# M705.net
KiCad netlist of a schematic drawn in EAGLE
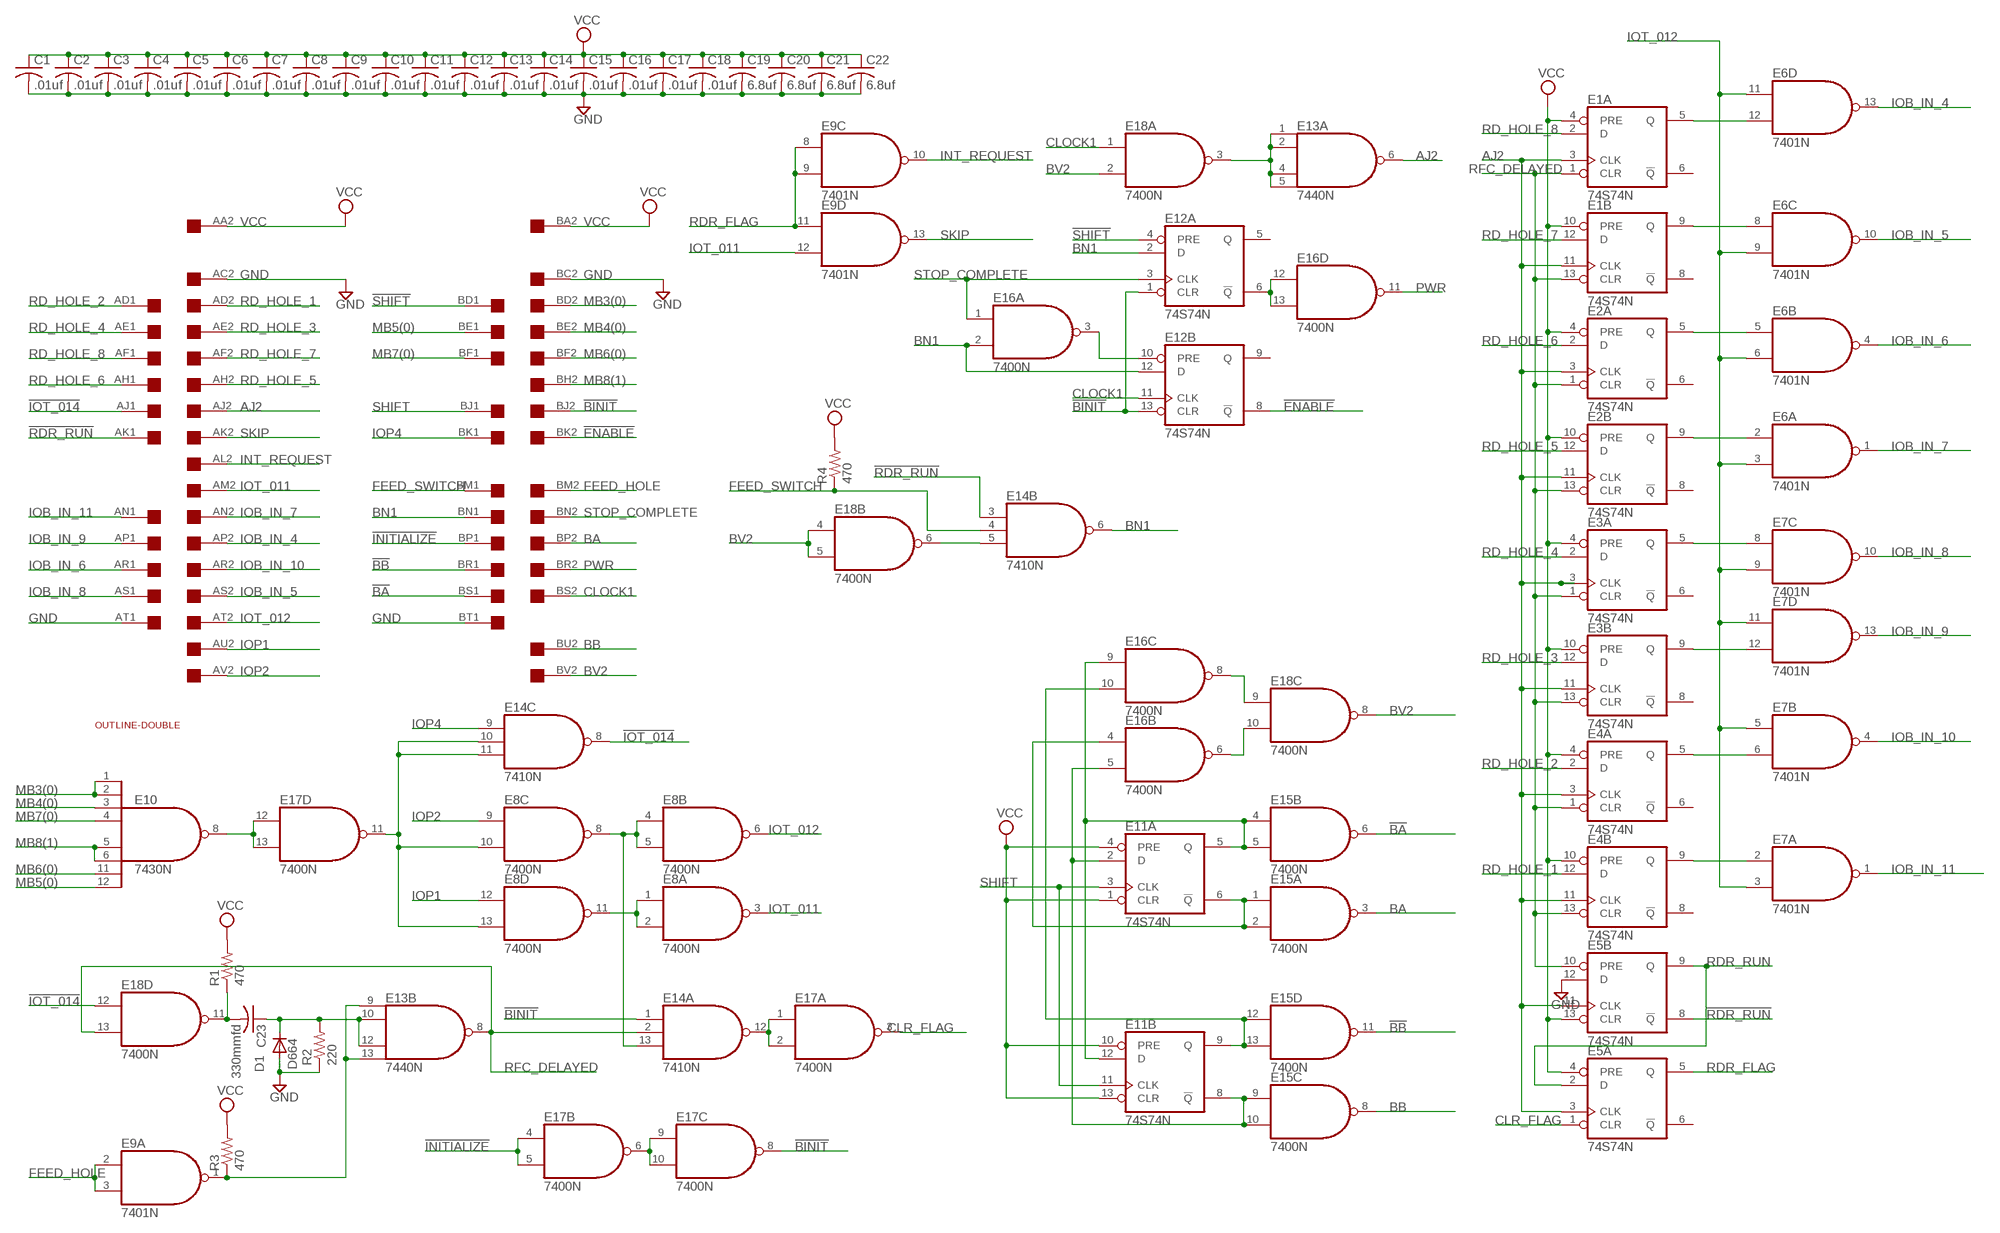
[diagram p0: schematic, sheet 1]

(export (version "E")
  (design (tool "Eeschema 10.0.6"))
  (components
    (comp (ref "C1")
      (value ".01uf")
      (footprint "eagle-import:C050-025X075")
      (libsource (lib "eagle-import") (part "C-US050-025X075"))
    )
    (comp (ref "C2")
      (value ".01uf")
      (footprint "eagle-import:C050-025X075")
      (libsource (lib "eagle-import") (part "C-US050-025X075"))
    )
    (comp (ref "C3")
      (value ".01uf")
      (footprint "eagle-import:C050-025X075")
      (libsource (lib "eagle-import") (part "C-US050-025X075"))
    )
    (comp (ref "C4")
      (value ".01uf")
      (footprint "eagle-import:C050-025X075")
      (libsource (lib "eagle-import") (part "C-US050-025X075"))
    )
    (comp (ref "C5")
      (value ".01uf")
      (footprint "eagle-import:C050-025X075")
      (libsource (lib "eagle-import") (part "C-US050-025X075"))
    )
    (comp (ref "C6")
      (value ".01uf")
      (footprint "eagle-import:C050-025X075")
      (libsource (lib "eagle-import") (part "C-US050-025X075"))
    )
    (comp (ref "C7")
      (value ".01uf")
      (footprint "eagle-import:C050-025X075")
      (libsource (lib "eagle-import") (part "C-US050-025X075"))
    )
    (comp (ref "C8")
      (value ".01uf")
      (footprint "eagle-import:C050-025X075")
      (libsource (lib "eagle-import") (part "C-US050-025X075"))
    )
    (comp (ref "C9")
      (value ".01uf")
      (footprint "eagle-import:C050-025X075")
      (libsource (lib "eagle-import") (part "C-US050-025X075"))
    )
    (comp (ref "C10")
      (value ".01uf")
      (footprint "eagle-import:C050-025X075")
      (libsource (lib "eagle-import") (part "C-US050-025X075"))
    )
    (comp (ref "C11")
      (value ".01uf")
      (footprint "eagle-import:C050-025X075")
      (libsource (lib "eagle-import") (part "C-US050-025X075"))
    )
    (comp (ref "C12")
      (value ".01uf")
      (footprint "eagle-import:C050-025X075")
      (libsource (lib "eagle-import") (part "C-US050-025X075"))
    )
    (comp (ref "C13")
      (value ".01uf")
      (footprint "eagle-import:C050-025X075")
      (libsource (lib "eagle-import") (part "C-US050-025X075"))
    )
    (comp (ref "C14")
      (value ".01uf")
      (footprint "eagle-import:C050-025X075")
      (libsource (lib "eagle-import") (part "C-US050-025X075"))
    )
    (comp (ref "C15")
      (value ".01uf")
      (footprint "eagle-import:C050-025X075")
      (libsource (lib "eagle-import") (part "C-US050-025X075"))
    )
    (comp (ref "C16")
      (value ".01uf")
      (footprint "eagle-import:C050-025X075")
      (libsource (lib "eagle-import") (part "C-US050-025X075"))
    )
    (comp (ref "C17")
      (value ".01uf")
      (footprint "eagle-import:C050-025X075")
      (libsource (lib "eagle-import") (part "C-US050-025X075"))
    )
    (comp (ref "C18")
      (value ".01uf")
      (footprint "eagle-import:C050-025X075")
      (libsource (lib "eagle-import") (part "C-US050-025X075"))
    )
    (comp (ref "C19")
      (value "6.8uf")
      (footprint "eagle-import:C150-054X183")
      (libsource (lib "eagle-import") (part "C-US150-054X183"))
    )
    (comp (ref "C20")
      (value "6.8uf")
      (footprint "eagle-import:C150-054X183")
      (libsource (lib "eagle-import") (part "C-US150-054X183"))
    )
    (comp (ref "C21")
      (value "6.8uf")
      (footprint "eagle-import:C150-054X183")
      (libsource (lib "eagle-import") (part "C-US150-054X183"))
    )
    (comp (ref "C22")
      (value "6.8uf")
      (footprint "eagle-import:C150-054X183")
      (libsource (lib "eagle-import") (part "C-US150-054X183"))
    )
    (comp (ref "C23")
      (value "330mmfd")
      (footprint "eagle-import:C050-025X075")
      (libsource (lib "eagle-import") (part "C-US050-025X075"))
    )
    (comp (ref "D1")
      (value "D664")
      (footprint "eagle-import:DO35-10")
      (libsource (lib "eagle-import") (part "1N4148DO35-10"))
    )
    (comp (ref "E1")
      (value "74S74N")
      (footprint "eagle-import:DIL14")
      (libsource (lib "eagle-import") (part "7474NS"))
    )
    (comp (ref "E2")
      (value "74S74N")
      (footprint "eagle-import:DIL14")
      (libsource (lib "eagle-import") (part "7474NS"))
    )
    (comp (ref "E3")
      (value "74S74N")
      (footprint "eagle-import:DIL14")
      (libsource (lib "eagle-import") (part "7474NS"))
    )
    (comp (ref "E4")
      (value "74S74N")
      (footprint "eagle-import:DIL14")
      (libsource (lib "eagle-import") (part "7474NS"))
    )
    (comp (ref "E5")
      (value "74S74N")
      (footprint "eagle-import:DIL14")
      (libsource (lib "eagle-import") (part "7474NS"))
    )
    (comp (ref "E6")
      (value "7401N")
      (footprint "eagle-import:DIL14")
      (libsource (lib "eagle-import") (part "7401NLS"))
    )
    (comp (ref "E7")
      (value "7401N")
      (footprint "eagle-import:DIL14")
      (libsource (lib "eagle-import") (part "7401NLS"))
    )
    (comp (ref "E8")
      (value "7400N")
      (footprint "eagle-import:DIL14")
      (libsource (lib "eagle-import") (part "7400N"))
    )
    (comp (ref "E9")
      (value "7401N")
      (footprint "eagle-import:DIL14")
      (libsource (lib "eagle-import") (part "7401NLS"))
    )
    (comp (ref "E10")
      (value "7430N")
      (footprint "eagle-import:DIL14")
      (libsource (lib "eagle-import") (part "7430N"))
    )
    (comp (ref "E11")
      (value "74S74N")
      (footprint "eagle-import:DIL14")
      (libsource (lib "eagle-import") (part "7474NS"))
    )
    (comp (ref "E12")
      (value "74S74N")
      (footprint "eagle-import:DIL14")
      (libsource (lib "eagle-import") (part "7474NS"))
    )
    (comp (ref "E13")
      (value "7440N")
      (footprint "eagle-import:DIL14")
      (libsource (lib "eagle-import") (part "7420NS"))
    )
    (comp (ref "E14")
      (value "7410N")
      (footprint "eagle-import:DIL14")
      (libsource (lib "eagle-import") (part "7410N"))
    )
    (comp (ref "E15")
      (value "7400N")
      (footprint "eagle-import:DIL14")
      (libsource (lib "eagle-import") (part "7400N"))
    )
    (comp (ref "E16")
      (value "7400N")
      (footprint "eagle-import:DIL14")
      (libsource (lib "eagle-import") (part "7400N"))
    )
    (comp (ref "E17")
      (value "7400N")
      (footprint "eagle-import:DIL14")
      (libsource (lib "eagle-import") (part "7400N"))
    )
    (comp (ref "E18")
      (value "7400N")
      (footprint "eagle-import:DIL14")
      (libsource (lib "eagle-import") (part "7400N"))
    )
    (comp (ref "R1")
      (value "470")
      (footprint "eagle-import:0207_10")
      (libsource (lib "eagle-import") (part "R-US_0207/10"))
    )
    (comp (ref "R2")
      (value "220")
      (footprint "eagle-import:0207_10")
      (libsource (lib "eagle-import") (part "R-US_0207/10"))
    )
    (comp (ref "R3")
      (value "470")
      (footprint "eagle-import:0207_10")
      (libsource (lib "eagle-import") (part "R-US_0207/10"))
    )
    (comp (ref "R4")
      (value "470")
      (footprint "eagle-import:0207_10")
      (libsource (lib "eagle-import") (part "R-US_0207/10"))
    )
    (comp (ref "U$5")
      (value "DOUBLE")
      (footprint "eagle-import:EDGE-CON4")
      (libsource (lib "eagle-import") (part "DOUBLE"))
    )
    (comp (ref "U$6")
      (value "OUTLINE-DOUBLE")
      (footprint "eagle-import:DOUBLE")
      (libsource (lib "eagle-import") (part "OUTLINE-DOUBLE"))
    )
  )
  (nets
    (net (code "1") (name "/AJ2") (class "Default")
      (node (ref "E1") (pin "11") (pinfunction "CLK_11") (pintype "input"))
      (node (ref "E1") (pin "3") (pinfunction "CLK_3") (pintype "input"))
      (node (ref "E13") (pin "6") (pinfunction "O_6") (pintype "output"))
      (node (ref "E2") (pin "11") (pinfunction "CLK_11") (pintype "input"))
      (node (ref "E2") (pin "3") (pinfunction "CLK_3") (pintype "input"))
      (node (ref "E3") (pin "11") (pinfunction "CLK_11") (pintype "input"))
      (node (ref "E3") (pin "3") (pinfunction "CLK_3") (pintype "input"))
      (node (ref "E4") (pin "11") (pinfunction "CLK_11") (pintype "input"))
      (node (ref "E4") (pin "3") (pinfunction "CLK_3") (pintype "input"))
      (node (ref "E5") (pin "11") (pinfunction "CLK_11") (pintype "input"))
      (node (ref "E5") (pin "3") (pinfunction "CLK_3") (pintype "input"))
      (node (ref "U$5") (pin "AJ2") (pinfunction "1_AJ2") (pintype "bidirectional"))
    )
    (net (code "2") (name "/BA") (class "Default")
      (node (ref "E15") (pin "3") (pinfunction "O_3") (pintype "output"))
      (node (ref "U$5") (pin "BP2") (pinfunction "1_BP2") (pintype "bidirectional"))
    )
    (net (code "3") (name "/BB") (class "Default")
      (node (ref "E15") (pin "8") (pinfunction "O_8") (pintype "output"))
      (node (ref "U$5") (pin "BU2") (pinfunction "1_BU2") (pintype "bidirectional"))
    )
    (net (code "4") (name "/BN1") (class "Default")
      (node (ref "E12") (pin "12") (pinfunction "D_12") (pintype "input"))
      (node (ref "E12") (pin "2") (pinfunction "D_2") (pintype "input"))
      (node (ref "E14") (pin "6") (pinfunction "O_6") (pintype "output"))
      (node (ref "E16") (pin "2") (pinfunction "I1_2") (pintype "input"))
      (node (ref "U$5") (pin "BN1") (pinfunction "1_BN1") (pintype "bidirectional"))
    )
    (net (code "5") (name "/BV2") (class "Default")
      (node (ref "E18") (pin "2") (pinfunction "I1_2") (pintype "input"))
      (node (ref "E18") (pin "4") (pinfunction "I0_4") (pintype "input"))
      (node (ref "E18") (pin "5") (pinfunction "I1_5") (pintype "input"))
      (node (ref "E18") (pin "8") (pinfunction "O_8") (pintype "output"))
      (node (ref "U$5") (pin "BV2") (pinfunction "1_BV2") (pintype "bidirectional"))
    )
    (net (code "6") (name "/CLOCK1") (class "Default")
      (node (ref "E12") (pin "11") (pinfunction "CLK_11") (pintype "input"))
      (node (ref "E18") (pin "1") (pinfunction "I0_1") (pintype "input"))
      (node (ref "U$5") (pin "BS2") (pinfunction "1_BS2") (pintype "bidirectional"))
    )
    (net (code "7") (name "/CLR_FLAG") (class "Default")
      (node (ref "E17") (pin "3") (pinfunction "O_3") (pintype "output"))
      (node (ref "E5") (pin "1") (pinfunction "CLR_1") (pintype "input"))
    )
    (net (code "8") (name "/FEED_HOLE") (class "Default")
      (node (ref "E9") (pin "2") (pinfunction "I0_2") (pintype "input"))
      (node (ref "E9") (pin "3") (pinfunction "I1_3") (pintype "input"))
      (node (ref "U$5") (pin "BM2") (pinfunction "1_BM2") (pintype "bidirectional"))
    )
    (net (code "9") (name "/FEED_SWITCH") (class "Default")
      (node (ref "E14") (pin "4") (pinfunction "I1_4") (pintype "input"))
      (node (ref "R4") (pin "1") (pinfunction "1_1") (pintype "passive"))
      (node (ref "U$5") (pin "BM1") (pinfunction "1_BM1") (pintype "bidirectional"))
    )
    (net (code "10") (name "/INT_REQUEST") (class "Default")
      (node (ref "E9") (pin "10") (pinfunction "O_10") (pintype "open_collector"))
      (node (ref "U$5") (pin "AL2") (pinfunction "1_AL2") (pintype "bidirectional"))
    )
    (net (code "11") (name "/IOB_IN_4") (class "Default")
      (node (ref "E6") (pin "13") (pinfunction "O_13") (pintype "open_collector"))
      (node (ref "U$5") (pin "AP2") (pinfunction "1_AP2") (pintype "bidirectional"))
    )
    (net (code "12") (name "/IOB_IN_5") (class "Default")
      (node (ref "E6") (pin "10") (pinfunction "O_10") (pintype "open_collector"))
      (node (ref "U$5") (pin "AS2") (pinfunction "1_AS2") (pintype "bidirectional"))
    )
    (net (code "13") (name "/IOB_IN_6") (class "Default")
      (node (ref "E6") (pin "4") (pinfunction "O_4") (pintype "open_collector"))
      (node (ref "U$5") (pin "AR1") (pinfunction "1_AR1") (pintype "bidirectional"))
    )
    (net (code "14") (name "/IOB_IN_7") (class "Default")
      (node (ref "E6") (pin "1") (pinfunction "O_1") (pintype "open_collector"))
      (node (ref "U$5") (pin "AN2") (pinfunction "1_AN2") (pintype "bidirectional"))
    )
    (net (code "15") (name "/IOB_IN_8") (class "Default")
      (node (ref "E7") (pin "10") (pinfunction "O_10") (pintype "open_collector"))
      (node (ref "U$5") (pin "AS1") (pinfunction "1_AS1") (pintype "bidirectional"))
    )
    (net (code "16") (name "/IOB_IN_9") (class "Default")
      (node (ref "E7") (pin "13") (pinfunction "O_13") (pintype "open_collector"))
      (node (ref "U$5") (pin "AP1") (pinfunction "1_AP1") (pintype "bidirectional"))
    )
    (net (code "17") (name "/IOB_IN_10") (class "Default")
      (node (ref "E7") (pin "4") (pinfunction "O_4") (pintype "open_collector"))
      (node (ref "U$5") (pin "AR2") (pinfunction "1_AR2") (pintype "bidirectional"))
    )
    (net (code "18") (name "/IOB_IN_11") (class "Default")
      (node (ref "E7") (pin "1") (pinfunction "O_1") (pintype "open_collector"))
      (node (ref "U$5") (pin "AN1") (pinfunction "1_AN1") (pintype "bidirectional"))
    )
    (net (code "19") (name "/IOP1") (class "Default")
      (node (ref "E8") (pin "12") (pinfunction "I0_12") (pintype "input"))
      (node (ref "U$5") (pin "AU2") (pinfunction "1_AU2") (pintype "bidirectional"))
    )
    (net (code "20") (name "/IOP2") (class "Default")
      (node (ref "E8") (pin "9") (pinfunction "I0_9") (pintype "input"))
      (node (ref "U$5") (pin "AV2") (pinfunction "1_AV2") (pintype "bidirectional"))
    )
    (net (code "21") (name "/IOP4") (class "Default")
      (node (ref "E14") (pin "9") (pinfunction "I0_9") (pintype "input"))
      (node (ref "U$5") (pin "BK1") (pinfunction "1_BK1") (pintype "bidirectional"))
    )
    (net (code "22") (name "/IOT_011") (class "Default")
      (node (ref "E8") (pin "3") (pinfunction "O_3") (pintype "output"))
      (node (ref "E9") (pin "12") (pinfunction "I1_12") (pintype "input"))
      (node (ref "U$5") (pin "AM2") (pinfunction "1_AM2") (pintype "bidirectional"))
    )
    (net (code "23") (name "/IOT_012") (class "Default")
      (node (ref "E6") (pin "11") (pinfunction "I0_11") (pintype "input"))
      (node (ref "E6") (pin "3") (pinfunction "I1_3") (pintype "input"))
      (node (ref "E6") (pin "6") (pinfunction "I1_6") (pintype "input"))
      (node (ref "E6") (pin "9") (pinfunction "I1_9") (pintype "input"))
      (node (ref "E7") (pin "11") (pinfunction "I0_11") (pintype "input"))
      (node (ref "E7") (pin "3") (pinfunction "I1_3") (pintype "input"))
      (node (ref "E7") (pin "5") (pinfunction "I0_5") (pintype "input"))
      (node (ref "E7") (pin "9") (pinfunction "I1_9") (pintype "input"))
      (node (ref "E8") (pin "6") (pinfunction "O_6") (pintype "output"))
      (node (ref "U$5") (pin "AT2") (pinfunction "1_AT2") (pintype "bidirectional"))
    )
    (net (code "24") (name "/MB3(0)") (class "Default")
      (node (ref "E10") (pin "1") (pinfunction "I0_1") (pintype "input"))
      (node (ref "E10") (pin "2") (pinfunction "I1_2") (pintype "input"))
      (node (ref "U$5") (pin "BD2") (pinfunction "1_BD2") (pintype "bidirectional"))
    )
    (net (code "25") (name "/MB4(0)") (class "Default")
      (node (ref "E10") (pin "3") (pinfunction "I2_3") (pintype "input"))
      (node (ref "U$5") (pin "BE2") (pinfunction "1_BE2") (pintype "bidirectional"))
    )
    (net (code "26") (name "/MB5(0)") (class "Default")
      (node (ref "E10") (pin "12") (pinfunction "I7_12") (pintype "input"))
      (node (ref "U$5") (pin "BE1") (pinfunction "1_BE1") (pintype "bidirectional"))
    )
    (net (code "27") (name "/MB6(0)") (class "Default")
      (node (ref "E10") (pin "11") (pinfunction "I6_11") (pintype "input"))
      (node (ref "U$5") (pin "BF2") (pinfunction "1_BF2") (pintype "bidirectional"))
    )
    (net (code "28") (name "/MB7(0)") (class "Default")
      (node (ref "E10") (pin "4") (pinfunction "I3_4") (pintype "input"))
      (node (ref "U$5") (pin "BF1") (pinfunction "1_BF1") (pintype "bidirectional"))
    )
    (net (code "29") (name "/MB8(1)") (class "Default")
      (node (ref "E10") (pin "5") (pinfunction "I4_5") (pintype "input"))
      (node (ref "E10") (pin "6") (pinfunction "I5_6") (pintype "input"))
      (node (ref "U$5") (pin "BH2") (pinfunction "1_BH2") (pintype "bidirectional"))
    )
    (net (code "30") (name "/PWR") (class "Default")
      (node (ref "E16") (pin "11") (pinfunction "O_11") (pintype "output"))
      (node (ref "U$5") (pin "BR2") (pinfunction "1_BR2") (pintype "bidirectional"))
    )
    (net (code "31") (name "/RDR_FLAG") (class "Default")
      (node (ref "E5") (pin "5") (pinfunction "Q_5") (pintype "output"))
      (node (ref "E9") (pin "11") (pinfunction "I0_11") (pintype "input"))
      (node (ref "E9") (pin "8") (pinfunction "I0_8") (pintype "input"))
      (node (ref "E9") (pin "9") (pinfunction "I1_9") (pintype "input"))
    )
    (net (code "32") (name "/RDR_RUN") (class "Default")
      (node (ref "E5") (pin "2") (pinfunction "D_2") (pintype "input"))
      (node (ref "E5") (pin "9") (pinfunction "Q_9") (pintype "output"))
    )
    (net (code "33") (name "/RD_HOLE_1") (class "Default")
      (node (ref "E4") (pin "12") (pinfunction "D_12") (pintype "input"))
      (node (ref "U$5") (pin "AD2") (pinfunction "1_AD2") (pintype "bidirectional"))
    )
    (net (code "34") (name "/RD_HOLE_2") (class "Default")
      (node (ref "E4") (pin "2") (pinfunction "D_2") (pintype "input"))
      (node (ref "U$5") (pin "AD1") (pinfunction "1_AD1") (pintype "bidirectional"))
    )
    (net (code "35") (name "/RD_HOLE_3") (class "Default")
      (node (ref "E3") (pin "12") (pinfunction "D_12") (pintype "input"))
      (node (ref "U$5") (pin "AE2") (pinfunction "1_AE2") (pintype "bidirectional"))
    )
    (net (code "36") (name "/RD_HOLE_4") (class "Default")
      (node (ref "E3") (pin "2") (pinfunction "D_2") (pintype "input"))
      (node (ref "U$5") (pin "AE1") (pinfunction "1_AE1") (pintype "bidirectional"))
    )
    (net (code "37") (name "/RD_HOLE_5") (class "Default")
      (node (ref "E2") (pin "12") (pinfunction "D_12") (pintype "input"))
      (node (ref "U$5") (pin "AH2") (pinfunction "1_AH2") (pintype "bidirectional"))
    )
    (net (code "38") (name "/RD_HOLE_6") (class "Default")
      (node (ref "E2") (pin "2") (pinfunction "D_2") (pintype "input"))
      (node (ref "U$5") (pin "AH1") (pinfunction "1_AH1") (pintype "bidirectional"))
    )
    (net (code "39") (name "/RD_HOLE_7") (class "Default")
      (node (ref "E1") (pin "12") (pinfunction "D_12") (pintype "input"))
      (node (ref "U$5") (pin "AF2") (pinfunction "1_AF2") (pintype "bidirectional"))
    )
    (net (code "40") (name "/RD_HOLE_8") (class "Default")
      (node (ref "E1") (pin "2") (pinfunction "D_2") (pintype "input"))
      (node (ref "U$5") (pin "AF1") (pinfunction "1_AF1") (pintype "bidirectional"))
    )
    (net (code "41") (name "/RFC_DELAYED") (class "Default")
      (node (ref "E1") (pin "1") (pinfunction "CLR_1") (pintype "input"))
      (node (ref "E1") (pin "13") (pinfunction "CLR_13") (pintype "input"))
      (node (ref "E13") (pin "8") (pinfunction "O_8") (pintype "output"))
      (node (ref "E14") (pin "2") (pinfunction "I1_2") (pintype "input"))
      (node (ref "E18") (pin "13") (pinfunction "I1_13") (pintype "input"))
      (node (ref "E2") (pin "1") (pinfunction "CLR_1") (pintype "input"))
      (node (ref "E2") (pin "13") (pinfunction "CLR_13") (pintype "input"))
      (node (ref "E3") (pin "1") (pinfunction "CLR_1") (pintype "input"))
      (node (ref "E3") (pin "13") (pinfunction "CLR_13") (pintype "input"))
      (node (ref "E4") (pin "1") (pinfunction "CLR_1") (pintype "input"))
      (node (ref "E4") (pin "13") (pinfunction "CLR_13") (pintype "input"))
      (node (ref "E5") (pin "10") (pinfunction "PRE_10") (pintype "input"))
    )
    (net (code "42") (name "/SHIFT") (class "Default")
      (node (ref "E11") (pin "11") (pinfunction "CLK_11") (pintype "input"))
      (node (ref "E11") (pin "3") (pinfunction "CLK_3") (pintype "input"))
      (node (ref "U$5") (pin "BJ1") (pinfunction "1_BJ1") (pintype "bidirectional"))
    )
    (net (code "43") (name "/SKIP") (class "Default")
      (node (ref "E9") (pin "13") (pinfunction "O_13") (pintype "open_collector"))
      (node (ref "U$5") (pin "AK2") (pinfunction "1_AK2") (pintype "bidirectional"))
    )
    (net (code "44") (name "/STOP_COMPLETE") (class "Default")
      (node (ref "E12") (pin "3") (pinfunction "CLK_3") (pintype "input"))
      (node (ref "E16") (pin "1") (pinfunction "I0_1") (pintype "input"))
      (node (ref "U$5") (pin "BN2") (pinfunction "1_BN2") (pintype "bidirectional"))
    )
    (net (code "45") (name "/~{BA}") (class "Default")
      (node (ref "E15") (pin "6") (pinfunction "O_6") (pintype "output"))
      (node (ref "U$5") (pin "BS1") (pinfunction "1_BS1") (pintype "bidirectional"))
    )
    (net (code "46") (name "/~{BB}") (class "Default")
      (node (ref "E15") (pin "11") (pinfunction "O_11") (pintype "output"))
      (node (ref "U$5") (pin "BR1") (pinfunction "1_BR1") (pintype "bidirectional"))
    )
    (net (code "47") (name "/~{BINIT}") (class "Default")
      (node (ref "E12") (pin "1") (pinfunction "CLR_1") (pintype "input"))
      (node (ref "E12") (pin "13") (pinfunction "CLR_13") (pintype "input"))
      (node (ref "E14") (pin "1") (pinfunction "I0_1") (pintype "input"))
      (node (ref "E17") (pin "8") (pinfunction "O_8") (pintype "output"))
      (node (ref "U$5") (pin "BJ2") (pinfunction "1_BJ2") (pintype "bidirectional"))
    )
    (net (code "48") (name "/~{ENABLE}") (class "Default")
      (node (ref "E12") (pin "8") (pinfunction "~{Q}_8") (pintype "output"))
      (node (ref "U$5") (pin "BK2") (pinfunction "1_BK2") (pintype "bidirectional"))
    )
    (net (code "49") (name "/~{INITIALIZE}") (class "Default")
      (node (ref "E17") (pin "4") (pinfunction "I0_4") (pintype "input"))
      (node (ref "E17") (pin "5") (pinfunction "I1_5") (pintype "input"))
      (node (ref "U$5") (pin "BP1") (pinfunction "1_BP1") (pintype "bidirectional"))
    )
    (net (code "50") (name "/~{IOT_014}") (class "Default")
      (node (ref "E14") (pin "8") (pinfunction "O_8") (pintype "output"))
      (node (ref "E18") (pin "12") (pinfunction "I0_12") (pintype "input"))
      (node (ref "U$5") (pin "AJ1") (pinfunction "1_AJ1") (pintype "bidirectional"))
    )
    (net (code "51") (name "/~{RDR_RUN}") (class "Default")
      (node (ref "E14") (pin "3") (pinfunction "I0_3") (pintype "input"))
      (node (ref "E5") (pin "8") (pinfunction "~{Q}_8") (pintype "output"))
      (node (ref "U$5") (pin "AK1") (pinfunction "1_AK1") (pintype "bidirectional"))
    )
    (net (code "52") (name "/~{SHIFT}") (class "Default")
      (node (ref "E12") (pin "4") (pinfunction "PRE_4") (pintype "input"))
      (node (ref "U$5") (pin "BD1") (pinfunction "1_BD1") (pintype "bidirectional"))
    )
    (net (code "53") (name "GND") (class "Default")
      (node (ref "C1") (pin "2") (pinfunction "2_2") (pintype "passive"))
      (node (ref "C10") (pin "2") (pinfunction "2_2") (pintype "passive"))
      (node (ref "C11") (pin "2") (pinfunction "2_2") (pintype "passive"))
      (node (ref "C12") (pin "2") (pinfunction "2_2") (pintype "passive"))
      (node (ref "C13") (pin "2") (pinfunction "2_2") (pintype "passive"))
      (node (ref "C14") (pin "2") (pinfunction "2_2") (pintype "passive"))
      (node (ref "C15") (pin "2") (pinfunction "2_2") (pintype "passive"))
      (node (ref "C16") (pin "2") (pinfunction "2_2") (pintype "passive"))
      (node (ref "C17") (pin "2") (pinfunction "2_2") (pintype "passive"))
      (node (ref "C18") (pin "2") (pinfunction "2_2") (pintype "passive"))
      (node (ref "C19") (pin "2") (pinfunction "2_2") (pintype "passive"))
      (node (ref "C2") (pin "2") (pinfunction "2_2") (pintype "passive"))
      (node (ref "C20") (pin "2") (pinfunction "2_2") (pintype "passive"))
      (node (ref "C21") (pin "2") (pinfunction "2_2") (pintype "passive"))
      (node (ref "C22") (pin "2") (pinfunction "2_2") (pintype "passive"))
      (node (ref "C3") (pin "2") (pinfunction "2_2") (pintype "passive"))
      (node (ref "C4") (pin "2") (pinfunction "2_2") (pintype "passive"))
      (node (ref "C5") (pin "2") (pinfunction "2_2") (pintype "passive"))
      (node (ref "C6") (pin "2") (pinfunction "2_2") (pintype "passive"))
      (node (ref "C7") (pin "2") (pinfunction "2_2") (pintype "passive"))
      (node (ref "C8") (pin "2") (pinfunction "2_2") (pintype "passive"))
      (node (ref "C9") (pin "2") (pinfunction "2_2") (pintype "passive"))
      (node (ref "D1") (pin "A") (pinfunction "A_A") (pintype "passive"))
      (node (ref "E5") (pin "12") (pinfunction "D_12") (pintype "input"))
      (node (ref "R2") (pin "1") (pinfunction "1_1") (pintype "passive"))
      (node (ref "U$5") (pin "AC2") (pinfunction "1_AC2") (pintype "bidirectional"))
      (node (ref "U$5") (pin "AT1") (pinfunction "1_AT1") (pintype "bidirectional"))
      (node (ref "U$5") (pin "BC2") (pinfunction "1_BC2") (pintype "bidirectional"))
      (node (ref "U$5") (pin "BT1") (pinfunction "1_BT1") (pintype "bidirectional"))
    )
    (net (code "54") (name "Net-(E1A-Q)") (class "Default")
      (node (ref "E1") (pin "5") (pinfunction "Q_5") (pintype "output"))
      (node (ref "E6") (pin "12") (pinfunction "I1_12") (pintype "input"))
    )
    (net (code "55") (name "Net-(E1B-Q)") (class "Default")
      (node (ref "E1") (pin "9") (pinfunction "Q_9") (pintype "output"))
      (node (ref "E6") (pin "8") (pinfunction "I0_8") (pintype "input"))
    )
    (net (code "56") (name "Net-(E2A-Q)") (class "Default")
      (node (ref "E2") (pin "5") (pinfunction "Q_5") (pintype "output"))
      (node (ref "E6") (pin "5") (pinfunction "I0_5") (pintype "input"))
    )
    (net (code "57") (name "Net-(E2B-Q)") (class "Default")
      (node (ref "E2") (pin "9") (pinfunction "Q_9") (pintype "output"))
      (node (ref "E6") (pin "2") (pinfunction "I0_2") (pintype "input"))
    )
    (net (code "58") (name "Net-(E3A-Q)") (class "Default")
      (node (ref "E3") (pin "5") (pinfunction "Q_5") (pintype "output"))
      (node (ref "E7") (pin "8") (pinfunction "I0_8") (pintype "input"))
    )
    (net (code "59") (name "Net-(E3B-Q)") (class "Default")
      (node (ref "E3") (pin "9") (pinfunction "Q_9") (pintype "output"))
      (node (ref "E7") (pin "12") (pinfunction "I1_12") (pintype "input"))
    )
    (net (code "60") (name "Net-(E4A-Q)") (class "Default")
      (node (ref "E4") (pin "5") (pinfunction "Q_5") (pintype "output"))
      (node (ref "E7") (pin "6") (pinfunction "I1_6") (pintype "input"))
    )
    (net (code "61") (name "Net-(E4B-Q)") (class "Default")
      (node (ref "E4") (pin "9") (pinfunction "Q_9") (pintype "output"))
      (node (ref "E7") (pin "2") (pinfunction "I0_2") (pintype "input"))
    )
    (net (code "62") (name "Net-(E8A-I0)") (class "Default")
      (node (ref "E8") (pin "1") (pinfunction "I0_1") (pintype "input"))
      (node (ref "E8") (pin "11") (pinfunction "O_11") (pintype "output"))
      (node (ref "E8") (pin "2") (pinfunction "I1_2") (pintype "input"))
    )
    (net (code "63") (name "Net-(E10A-O)") (class "Default")
      (node (ref "E10") (pin "8") (pinfunction "O_8") (pintype "output"))
      (node (ref "E17") (pin "12") (pinfunction "I0_12") (pintype "input"))
      (node (ref "E17") (pin "13") (pinfunction "I1_13") (pintype "input"))
    )
    (net (code "64") (name "Net-(E11A-D)") (class "Default")
      (node (ref "E11") (pin "2") (pinfunction "D_2") (pintype "input"))
      (node (ref "E11") (pin "8") (pinfunction "~{Q}_8") (pintype "output"))
      (node (ref "E15") (pin "10") (pinfunction "I1_10") (pintype "input"))
      (node (ref "E15") (pin "9") (pinfunction "I0_9") (pintype "input"))
      (node (ref "E16") (pin "5") (pinfunction "I1_5") (pintype "input"))
    )
    (net (code "65") (name "Net-(E11A-Q)") (class "Default")
      (node (ref "E11") (pin "12") (pinfunction "D_12") (pintype "input"))
      (node (ref "E11") (pin "5") (pinfunction "Q_5") (pintype "output"))
      (node (ref "E15") (pin "4") (pinfunction "I0_4") (pintype "input"))
      (node (ref "E15") (pin "5") (pinfunction "I1_5") (pintype "input"))
      (node (ref "E16") (pin "9") (pinfunction "I0_9") (pintype "input"))
    )
    (net (code "66") (name "Net-(E11A-~{Q})") (class "Default")
      (node (ref "E11") (pin "6") (pinfunction "~{Q}_6") (pintype "output"))
      (node (ref "E15") (pin "1") (pinfunction "I0_1") (pintype "input"))
      (node (ref "E15") (pin "2") (pinfunction "I1_2") (pintype "input"))
      (node (ref "E16") (pin "4") (pinfunction "I0_4") (pintype "input"))
    )
    (net (code "67") (name "Net-(E11B-Q)") (class "Default")
      (node (ref "E11") (pin "9") (pinfunction "Q_9") (pintype "output"))
      (node (ref "E15") (pin "12") (pinfunction "I0_12") (pintype "input"))
      (node (ref "E15") (pin "13") (pinfunction "I1_13") (pintype "input"))
      (node (ref "E16") (pin "10") (pinfunction "I1_10") (pintype "input"))
    )
    (net (code "68") (name "Net-(E12A-~{Q})") (class "Default")
      (node (ref "E12") (pin "6") (pinfunction "~{Q}_6") (pintype "output"))
      (node (ref "E16") (pin "12") (pinfunction "I0_12") (pintype "input"))
      (node (ref "E16") (pin "13") (pinfunction "I1_13") (pintype "input"))
    )
    (net (code "69") (name "Net-(E12B-PRE)") (class "Default")
      (node (ref "E12") (pin "10") (pinfunction "PRE_10") (pintype "input"))
      (node (ref "E16") (pin "3") (pinfunction "O_3") (pintype "output"))
    )
    (net (code "70") (name "Net-(E13A-I0)") (class "Default")
      (node (ref "E13") (pin "1") (pinfunction "I0_1") (pintype "input"))
      (node (ref "E13") (pin "2") (pinfunction "I1_2") (pintype "input"))
      (node (ref "E13") (pin "4") (pinfunction "I2_4") (pintype "input"))
      (node (ref "E13") (pin "5") (pinfunction "I3_5") (pintype "input"))
      (node (ref "E18") (pin "3") (pinfunction "O_3") (pintype "output"))
    )
    (net (code "71") (name "Net-(E13B-I0)") (class "Default")
      (node (ref "E13") (pin "13") (pinfunction "I3_13") (pintype "input"))
      (node (ref "E13") (pin "9") (pinfunction "I0_9") (pintype "input"))
      (node (ref "E9") (pin "1") (pinfunction "O_1") (pintype "open_collector"))
      (node (ref "R3") (pin "1") (pinfunction "1_1") (pintype "passive"))
    )
    (net (code "72") (name "Net-(E13B-I1)") (class "Default")
      (node (ref "C23") (pin "1") (pinfunction "1_1") (pintype "passive"))
      (node (ref "D1") (pin "C") (pinfunction "C_C") (pintype "passive"))
      (node (ref "E13") (pin "10") (pinfunction "I1_10") (pintype "input"))
      (node (ref "E13") (pin "12") (pinfunction "I2_12") (pintype "input"))
      (node (ref "R2") (pin "2") (pinfunction "2_2") (pintype "passive"))
    )
    (net (code "73") (name "Net-(E14A-I2)") (class "Default")
      (node (ref "E14") (pin "13") (pinfunction "I2_13") (pintype "input"))
      (node (ref "E8") (pin "4") (pinfunction "I0_4") (pintype "input"))
      (node (ref "E8") (pin "5") (pinfunction "I1_5") (pintype "input"))
      (node (ref "E8") (pin "8") (pinfunction "O_8") (pintype "output"))
    )
    (net (code "74") (name "Net-(E14A-O)") (class "Default")
      (node (ref "E14") (pin "12") (pinfunction "O_12") (pintype "output"))
      (node (ref "E17") (pin "1") (pinfunction "I0_1") (pintype "input"))
      (node (ref "E17") (pin "2") (pinfunction "I1_2") (pintype "input"))
    )
    (net (code "75") (name "Net-(E14B-I2)") (class "Default")
      (node (ref "E14") (pin "5") (pinfunction "I2_5") (pintype "input"))
      (node (ref "E18") (pin "6") (pinfunction "O_6") (pintype "output"))
    )
    (net (code "76") (name "Net-(E14C-I1)") (class "Default")
      (node (ref "E14") (pin "10") (pinfunction "I1_10") (pintype "input"))
      (node (ref "E14") (pin "11") (pinfunction "I2_11") (pintype "input"))
      (node (ref "E17") (pin "11") (pinfunction "O_11") (pintype "output"))
      (node (ref "E8") (pin "10") (pinfunction "I1_10") (pintype "input"))
      (node (ref "E8") (pin "13") (pinfunction "I1_13") (pintype "input"))
    )
    (net (code "77") (name "Net-(E16B-O)") (class "Default")
      (node (ref "E16") (pin "6") (pinfunction "O_6") (pintype "output"))
      (node (ref "E18") (pin "10") (pinfunction "I1_10") (pintype "input"))
    )
    (net (code "78") (name "Net-(E16C-O)") (class "Default")
      (node (ref "E16") (pin "8") (pinfunction "O_8") (pintype "output"))
      (node (ref "E18") (pin "9") (pinfunction "I0_9") (pintype "input"))
    )
    (net (code "79") (name "Net-(E17B-O)") (class "Default")
      (node (ref "E17") (pin "10") (pinfunction "I1_10") (pintype "input"))
      (node (ref "E17") (pin "6") (pinfunction "O_6") (pintype "output"))
      (node (ref "E17") (pin "9") (pinfunction "I0_9") (pintype "input"))
    )
    (net (code "80") (name "Net-(E18D-O)") (class "Default")
      (node (ref "C23") (pin "2") (pinfunction "2_2") (pintype "passive"))
      (node (ref "E18") (pin "11") (pinfunction "O_11") (pintype "output"))
      (node (ref "R1") (pin "1") (pinfunction "1_1") (pintype "passive"))
    )
    (net (code "81") (name "VCC") (class "Default")
      (node (ref "C1") (pin "1") (pinfunction "1_1") (pintype "passive"))
      (node (ref "C10") (pin "1") (pinfunction "1_1") (pintype "passive"))
      (node (ref "C11") (pin "1") (pinfunction "1_1") (pintype "passive"))
      (node (ref "C12") (pin "1") (pinfunction "1_1") (pintype "passive"))
      (node (ref "C13") (pin "1") (pinfunction "1_1") (pintype "passive"))
      (node (ref "C14") (pin "1") (pinfunction "1_1") (pintype "passive"))
      (node (ref "C15") (pin "1") (pinfunction "1_1") (pintype "passive"))
      (node (ref "C16") (pin "1") (pinfunction "1_1") (pintype "passive"))
      (node (ref "C17") (pin "1") (pinfunction "1_1") (pintype "passive"))
      (node (ref "C18") (pin "1") (pinfunction "1_1") (pintype "passive"))
      (node (ref "C19") (pin "1") (pinfunction "1_1") (pintype "passive"))
      (node (ref "C2") (pin "1") (pinfunction "1_1") (pintype "passive"))
      (node (ref "C20") (pin "1") (pinfunction "1_1") (pintype "passive"))
      (node (ref "C21") (pin "1") (pinfunction "1_1") (pintype "passive"))
      (node (ref "C22") (pin "1") (pinfunction "1_1") (pintype "passive"))
      (node (ref "C3") (pin "1") (pinfunction "1_1") (pintype "passive"))
      (node (ref "C4") (pin "1") (pinfunction "1_1") (pintype "passive"))
      (node (ref "C5") (pin "1") (pinfunction "1_1") (pintype "passive"))
      (node (ref "C6") (pin "1") (pinfunction "1_1") (pintype "passive"))
      (node (ref "C7") (pin "1") (pinfunction "1_1") (pintype "passive"))
      (node (ref "C8") (pin "1") (pinfunction "1_1") (pintype "passive"))
      (node (ref "C9") (pin "1") (pinfunction "1_1") (pintype "passive"))
      (node (ref "E1") (pin "10") (pinfunction "PRE_10") (pintype "input"))
      (node (ref "E1") (pin "4") (pinfunction "PRE_4") (pintype "input"))
      (node (ref "E11") (pin "1") (pinfunction "CLR_1") (pintype "input"))
      (node (ref "E11") (pin "10") (pinfunction "PRE_10") (pintype "input"))
      (node (ref "E11") (pin "13") (pinfunction "CLR_13") (pintype "input"))
      (node (ref "E11") (pin "4") (pinfunction "PRE_4") (pintype "input"))
      (node (ref "E2") (pin "10") (pinfunction "PRE_10") (pintype "input"))
      (node (ref "E2") (pin "4") (pinfunction "PRE_4") (pintype "input"))
      (node (ref "E3") (pin "10") (pinfunction "PRE_10") (pintype "input"))
      (node (ref "E3") (pin "4") (pinfunction "PRE_4") (pintype "input"))
      (node (ref "E4") (pin "10") (pinfunction "PRE_10") (pintype "input"))
      (node (ref "E4") (pin "4") (pinfunction "PRE_4") (pintype "input"))
      (node (ref "E5") (pin "13") (pinfunction "CLR_13") (pintype "input"))
      (node (ref "E5") (pin "4") (pinfunction "PRE_4") (pintype "input"))
      (node (ref "R1") (pin "2") (pinfunction "2_2") (pintype "passive"))
      (node (ref "R3") (pin "2") (pinfunction "2_2") (pintype "passive"))
      (node (ref "R4") (pin "2") (pinfunction "2_2") (pintype "passive"))
      (node (ref "U$5") (pin "AA2") (pinfunction "1_AA2") (pintype "bidirectional"))
      (node (ref "U$5") (pin "BA2") (pinfunction "1_BA2") (pintype "bidirectional"))
    )
    (net (code "82") (name "unconnected-(E1A-~{Q}-Pad6)") (class "Default")
      (node (ref "E1") (pin "6") (pinfunction "~{Q}_6") (pintype "output"))
    )
    (net (code "83") (name "unconnected-(E1B-~{Q}-Pad8)") (class "Default")
      (node (ref "E1") (pin "8") (pinfunction "~{Q}_8") (pintype "output"))
    )
    (net (code "84") (name "unconnected-(E2A-~{Q}-Pad6)") (class "Default")
      (node (ref "E2") (pin "6") (pinfunction "~{Q}_6") (pintype "output"))
    )
    (net (code "85") (name "unconnected-(E2B-~{Q}-Pad8)") (class "Default")
      (node (ref "E2") (pin "8") (pinfunction "~{Q}_8") (pintype "output"))
    )
    (net (code "86") (name "unconnected-(E3A-~{Q}-Pad6)") (class "Default")
      (node (ref "E3") (pin "6") (pinfunction "~{Q}_6") (pintype "output"))
    )
    (net (code "87") (name "unconnected-(E3B-~{Q}-Pad8)") (class "Default")
      (node (ref "E3") (pin "8") (pinfunction "~{Q}_8") (pintype "output"))
    )
    (net (code "88") (name "unconnected-(E4A-~{Q}-Pad6)") (class "Default")
      (node (ref "E4") (pin "6") (pinfunction "~{Q}_6") (pintype "output"))
    )
    (net (code "89") (name "unconnected-(E4B-~{Q}-Pad8)") (class "Default")
      (node (ref "E4") (pin "8") (pinfunction "~{Q}_8") (pintype "output"))
    )
    (net (code "90") (name "unconnected-(E5A-~{Q}-Pad6)") (class "Default")
      (node (ref "E5") (pin "6") (pinfunction "~{Q}_6") (pintype "output"))
    )
    (net (code "91") (name "unconnected-(E12A-Q-Pad5)") (class "Default")
      (node (ref "E12") (pin "5") (pinfunction "Q_5") (pintype "output"))
    )
    (net (code "92") (name "unconnected-(E12B-Q-Pad9)") (class "Default")
      (node (ref "E12") (pin "9") (pinfunction "Q_9") (pintype "output"))
    )
  )
)
